# tabdil_motor.net
KiCad netlist of a schematic drawn in Altium Designer
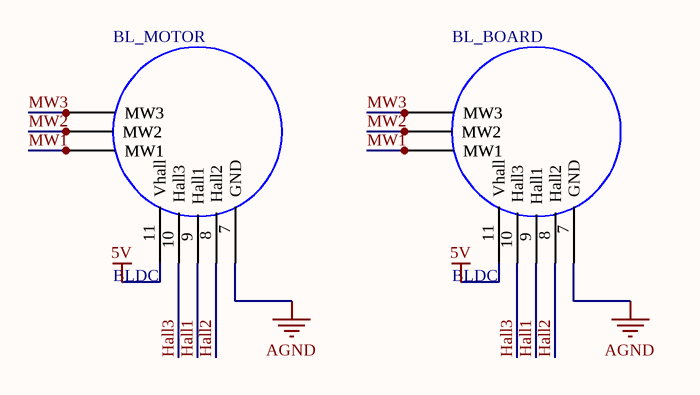
[diagram p0: tabdil motor.SchDoc]

(export (version "E")
  (design (tool "Eeschema 10.0.6"))
  (components
    (comp (ref "BL_BOARD") (value "BLDC") (footprint "FLT11") (libsource (lib "KN2CLib") (part "BLDC")))
    (comp (ref "BL_MOTOR") (value "BLDC") (footprint "FLT11") (libsource (lib "KN2CLib") (part "BLDC")))
  )
  (nets
    (net (code "1") (name "/Hall1") (class "Default")
      (node (ref "BL_BOARD") (pin "9") (pinfunction "Hall1_9") (pintype "passive"))
      (node (ref "BL_MOTOR") (pin "9") (pinfunction "Hall1_9") (pintype "passive"))
    )
    (net (code "2") (name "/Hall2") (class "Default")
      (node (ref "BL_BOARD") (pin "8") (pinfunction "Hall2_8") (pintype "passive"))
      (node (ref "BL_MOTOR") (pin "8") (pinfunction "Hall2_8") (pintype "passive"))
    )
    (net (code "3") (name "/Hall3") (class "Default")
      (node (ref "BL_BOARD") (pin "10") (pinfunction "Hall3_10") (pintype "passive"))
      (node (ref "BL_MOTOR") (pin "10") (pinfunction "Hall3_10") (pintype "passive"))
    )
    (net (code "4") (name "/MW1") (class "Default")
      (node (ref "BL_BOARD") (pin "1") (pinfunction "MW1_1") (pintype "passive"))
      (node (ref "BL_BOARD") (pin "2") (pinfunction "MW1_2") (pintype "passive"))
      (node (ref "BL_MOTOR") (pin "1") (pinfunction "MW1_1") (pintype "passive"))
      (node (ref "BL_MOTOR") (pin "2") (pinfunction "MW1_2") (pintype "passive"))
    )
    (net (code "5") (name "/MW2") (class "Default")
      (node (ref "BL_BOARD") (pin "3") (pinfunction "MW2_3") (pintype "passive"))
      (node (ref "BL_BOARD") (pin "4") (pinfunction "MW2_4") (pintype "passive"))
      (node (ref "BL_MOTOR") (pin "3") (pinfunction "MW2_3") (pintype "passive"))
      (node (ref "BL_MOTOR") (pin "4") (pinfunction "MW2_4") (pintype "passive"))
    )
    (net (code "6") (name "/MW3") (class "Default")
      (node (ref "BL_BOARD") (pin "5") (pinfunction "MW3_5") (pintype "passive"))
      (node (ref "BL_BOARD") (pin "6") (pinfunction "MW3_6") (pintype "passive"))
      (node (ref "BL_MOTOR") (pin "5") (pinfunction "MW3_5") (pintype "passive"))
      (node (ref "BL_MOTOR") (pin "6") (pinfunction "MW3_6") (pintype "passive"))
    )
    (net (code "7") (name "5V") (class "Default")
      (node (ref "BL_BOARD") (pin "11") (pinfunction "Vhall_11") (pintype "passive"))
      (node (ref "BL_MOTOR") (pin "11") (pinfunction "Vhall_11") (pintype "passive"))
    )
    (net (code "8") (name "AGND") (class "Default")
      (node (ref "BL_BOARD") (pin "7") (pinfunction "GND_7") (pintype "passive"))
      (node (ref "BL_MOTOR") (pin "7") (pinfunction "GND_7") (pintype "passive"))
    )
  )
)
